# Shield_3up.net
KiCad netlist of a schematic drawn in EAGLE
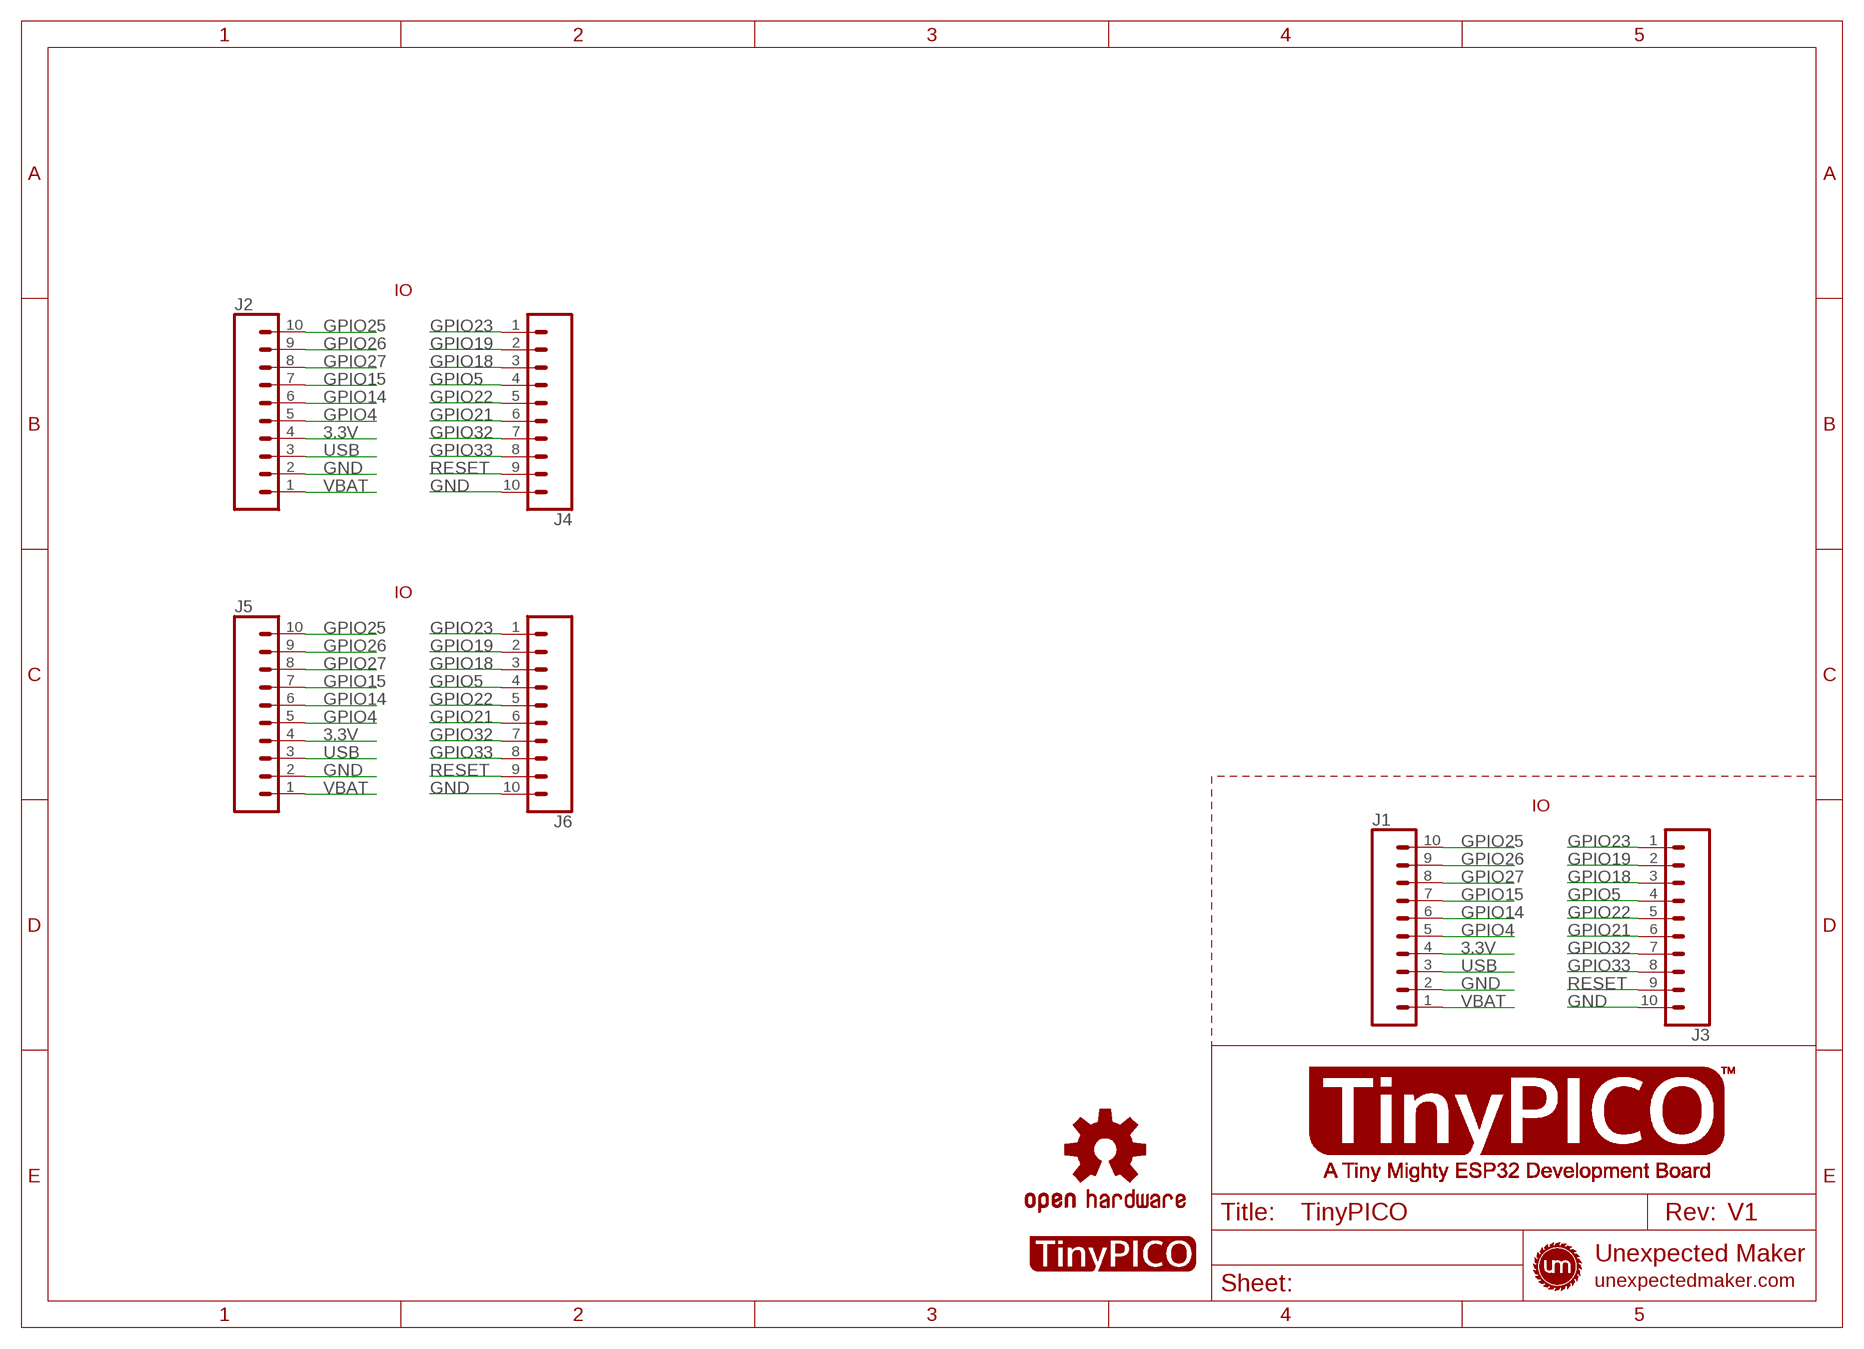
[diagram p0: schematic, sheet 1]

(export (version "E")
  (design (tool "Eeschema 10.0.6"))
  (components
    (comp (ref "J1")
      (value "TINYPICO_HEADER_10NO_SILK_PTH_FEMALE")
      (footprint "eagle-import:1X10_NO_SILK")
      (libsource (lib "eagle-import") (part "TINYPICO_HEADER_10NO_SILK_PTH_FEMALE"))
    )
    (comp (ref "J2")
      (value "TINYPICO_HEADER_10NO_SILK_PTH_FEMALE")
      (footprint "eagle-import:1X10_NO_SILK")
      (libsource (lib "eagle-import") (part "TINYPICO_HEADER_10NO_SILK_PTH_FEMALE"))
    )
    (comp (ref "J3")
      (value "TINYPICO_HEADER_10NO_SILK_PTH_FEMALE")
      (footprint "eagle-import:1X10_NO_SILK")
      (libsource (lib "eagle-import") (part "TINYPICO_HEADER_10NO_SILK_PTH_FEMALE"))
    )
    (comp (ref "J4")
      (value "TINYPICO_HEADER_10NO_SILK_PTH_FEMALE")
      (footprint "eagle-import:1X10_NO_SILK")
      (libsource (lib "eagle-import") (part "TINYPICO_HEADER_10NO_SILK_PTH_FEMALE"))
    )
    (comp (ref "J5")
      (value "TINYPICO_HEADER_10NO_SILK_PTH_FEMALE")
      (footprint "eagle-import:1X10_NO_SILK")
      (libsource (lib "eagle-import") (part "TINYPICO_HEADER_10NO_SILK_PTH_FEMALE"))
    )
    (comp (ref "J6")
      (value "TINYPICO_HEADER_10NO_SILK_PTH_FEMALE")
      (footprint "eagle-import:1X10_NO_SILK")
      (libsource (lib "eagle-import") (part "TINYPICO_HEADER_10NO_SILK_PTH_FEMALE"))
    )
    (comp (ref "LOGO1")
      (value "OSHW-LOGOS")
      (footprint "eagle-import:OSHW-LOGO-S")
      (libsource (lib "eagle-import") (part "OSHW-LOGOS"))
    )
    (comp (ref "U$1")
      (value "TP_LOGO")
      (footprint "eagle-import:TP_LOGO")
      (libsource (lib "eagle-import") (part "TP_LOGO"))
    )
  )
  (nets
    (net (code "1") (name "/3.3V") (class "Default")
      (node (ref "J1") (pin "4") (pinfunction "4_4") (pintype "passive"))
      (node (ref "J2") (pin "4") (pinfunction "4_4") (pintype "passive"))
      (node (ref "J5") (pin "4") (pinfunction "4_4") (pintype "passive"))
    )
    (net (code "2") (name "/GND") (class "Default")
      (node (ref "J1") (pin "2") (pinfunction "2_2") (pintype "passive"))
      (node (ref "J2") (pin "2") (pinfunction "2_2") (pintype "passive"))
      (node (ref "J3") (pin "10") (pinfunction "10_10") (pintype "passive"))
      (node (ref "J4") (pin "10") (pinfunction "10_10") (pintype "passive"))
      (node (ref "J5") (pin "2") (pinfunction "2_2") (pintype "passive"))
      (node (ref "J6") (pin "10") (pinfunction "10_10") (pintype "passive"))
    )
    (net (code "3") (name "/GPIO4") (class "Default")
      (node (ref "J1") (pin "5") (pinfunction "5_5") (pintype "passive"))
      (node (ref "J2") (pin "5") (pinfunction "5_5") (pintype "passive"))
      (node (ref "J5") (pin "5") (pinfunction "5_5") (pintype "passive"))
    )
    (net (code "4") (name "/GPIO5") (class "Default")
      (node (ref "J3") (pin "4") (pinfunction "4_4") (pintype "passive"))
      (node (ref "J4") (pin "4") (pinfunction "4_4") (pintype "passive"))
      (node (ref "J6") (pin "4") (pinfunction "4_4") (pintype "passive"))
    )
    (net (code "5") (name "/GPIO14") (class "Default")
      (node (ref "J1") (pin "6") (pinfunction "6_6") (pintype "passive"))
      (node (ref "J2") (pin "6") (pinfunction "6_6") (pintype "passive"))
      (node (ref "J5") (pin "6") (pinfunction "6_6") (pintype "passive"))
    )
    (net (code "6") (name "/GPIO15") (class "Default")
      (node (ref "J1") (pin "7") (pinfunction "7_7") (pintype "passive"))
      (node (ref "J2") (pin "7") (pinfunction "7_7") (pintype "passive"))
      (node (ref "J5") (pin "7") (pinfunction "7_7") (pintype "passive"))
    )
    (net (code "7") (name "/GPIO18") (class "Default")
      (node (ref "J3") (pin "3") (pinfunction "3_3") (pintype "passive"))
      (node (ref "J4") (pin "3") (pinfunction "3_3") (pintype "passive"))
      (node (ref "J6") (pin "3") (pinfunction "3_3") (pintype "passive"))
    )
    (net (code "8") (name "/GPIO19") (class "Default")
      (node (ref "J3") (pin "2") (pinfunction "2_2") (pintype "passive"))
      (node (ref "J4") (pin "2") (pinfunction "2_2") (pintype "passive"))
      (node (ref "J6") (pin "2") (pinfunction "2_2") (pintype "passive"))
    )
    (net (code "9") (name "/GPIO21") (class "Default")
      (node (ref "J3") (pin "6") (pinfunction "6_6") (pintype "passive"))
      (node (ref "J4") (pin "6") (pinfunction "6_6") (pintype "passive"))
      (node (ref "J6") (pin "6") (pinfunction "6_6") (pintype "passive"))
    )
    (net (code "10") (name "/GPIO22") (class "Default")
      (node (ref "J3") (pin "5") (pinfunction "5_5") (pintype "passive"))
      (node (ref "J4") (pin "5") (pinfunction "5_5") (pintype "passive"))
      (node (ref "J6") (pin "5") (pinfunction "5_5") (pintype "passive"))
    )
    (net (code "11") (name "/GPIO23") (class "Default")
      (node (ref "J3") (pin "1") (pinfunction "1_1") (pintype "passive"))
      (node (ref "J4") (pin "1") (pinfunction "1_1") (pintype "passive"))
      (node (ref "J6") (pin "1") (pinfunction "1_1") (pintype "passive"))
    )
    (net (code "12") (name "/GPIO25") (class "Default")
      (node (ref "J1") (pin "10") (pinfunction "10_10") (pintype "passive"))
      (node (ref "J2") (pin "10") (pinfunction "10_10") (pintype "passive"))
      (node (ref "J5") (pin "10") (pinfunction "10_10") (pintype "passive"))
    )
    (net (code "13") (name "/GPIO26") (class "Default")
      (node (ref "J1") (pin "9") (pinfunction "9_9") (pintype "passive"))
      (node (ref "J2") (pin "9") (pinfunction "9_9") (pintype "passive"))
      (node (ref "J5") (pin "9") (pinfunction "9_9") (pintype "passive"))
    )
    (net (code "14") (name "/GPIO27") (class "Default")
      (node (ref "J1") (pin "8") (pinfunction "8_8") (pintype "passive"))
      (node (ref "J2") (pin "8") (pinfunction "8_8") (pintype "passive"))
      (node (ref "J5") (pin "8") (pinfunction "8_8") (pintype "passive"))
    )
    (net (code "15") (name "/GPIO32") (class "Default")
      (node (ref "J3") (pin "7") (pinfunction "7_7") (pintype "passive"))
      (node (ref "J4") (pin "7") (pinfunction "7_7") (pintype "passive"))
      (node (ref "J6") (pin "7") (pinfunction "7_7") (pintype "passive"))
    )
    (net (code "16") (name "/GPIO33") (class "Default")
      (node (ref "J3") (pin "8") (pinfunction "8_8") (pintype "passive"))
      (node (ref "J4") (pin "8") (pinfunction "8_8") (pintype "passive"))
      (node (ref "J6") (pin "8") (pinfunction "8_8") (pintype "passive"))
    )
    (net (code "17") (name "/RESET") (class "Default")
      (node (ref "J3") (pin "9") (pinfunction "9_9") (pintype "passive"))
      (node (ref "J4") (pin "9") (pinfunction "9_9") (pintype "passive"))
      (node (ref "J6") (pin "9") (pinfunction "9_9") (pintype "passive"))
    )
    (net (code "18") (name "/USB") (class "Default")
      (node (ref "J1") (pin "3") (pinfunction "3_3") (pintype "passive"))
      (node (ref "J2") (pin "3") (pinfunction "3_3") (pintype "passive"))
      (node (ref "J5") (pin "3") (pinfunction "3_3") (pintype "passive"))
    )
    (net (code "19") (name "/VBAT") (class "Default")
      (node (ref "J1") (pin "1") (pinfunction "1_1") (pintype "passive"))
      (node (ref "J2") (pin "1") (pinfunction "1_1") (pintype "passive"))
      (node (ref "J5") (pin "1") (pinfunction "1_1") (pintype "passive"))
    )
  )
)
